# 5V_3V_LDO.net
KiCad netlist of a schematic drawn in Altium Designer
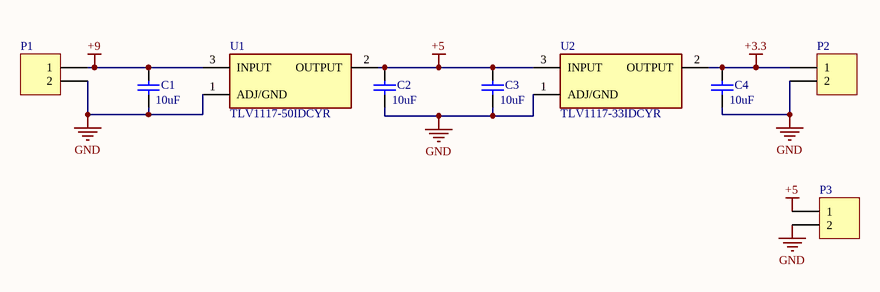
[diagram p0: 5V_3V_LDO.SchDoc]

(export (version "E")
  (design (tool "Eeschema 10.0.6"))
  (components
    (comp (ref "C1")
      (value "10uF")
      (footprint "0805 - Capacitor")
      (description "Nonpolarized Capacitor")
      (fields
        (field (name "MANUFACTURER") "Yageo")
        (field (name "MANUFACTURER PART NUMBER") "CC0805KKX5R8BB106")
      )
      (libsource (lib "General") (part "Capacitor - Nonpolarized"))
    )
    (comp (ref "C2")
      (value "10uF")
      (footprint "0805 - Capacitor")
      (description "Nonpolarized Capacitor")
      (fields
        (field (name "MANUFACTURER") "Yageo")
        (field (name "MANUFACTURER PART NUMBER") "CC0805KKX5R8BB106")
      )
      (libsource (lib "General") (part "Capacitor - Nonpolarized"))
    )
    (comp (ref "C3")
      (value "10uF")
      (footprint "0805 - Capacitor")
      (description "Nonpolarized Capacitor")
      (fields
        (field (name "MANUFACTURER") "Yageo")
        (field (name "MANUFACTURER PART NUMBER") "CC0805KKX5R8BB106")
      )
      (libsource (lib "General") (part "Capacitor - Nonpolarized"))
    )
    (comp (ref "C4")
      (value "10uF")
      (footprint "0805 - Capacitor")
      (description "Nonpolarized Capacitor")
      (fields
        (field (name "MANUFACTURER") "Yageo")
        (field (name "MANUFACTURER PART NUMBER") "CC0805KKX5R8BB106")
      )
      (libsource (lib "General") (part "Capacitor - Nonpolarized"))
    )
    (comp (ref "P1")
      (value "1x2 Header")
      (footprint "HDR1X2")
      (description "1x2 Pin Header")
      (libsource (lib "") (part "1x2 Header_1"))
    )
    (comp (ref "P2")
      (value "1x2 Header")
      (footprint "HDR1X2")
      (description "1x2 Pin Header")
      (libsource (lib "GeneralConnectors") (part "1x2 Header"))
    )
    (comp (ref "P3")
      (value "1x2 Header")
      (footprint "HDR1X2")
      (description "1x2 Pin Header")
      (libsource (lib "GeneralConnectors") (part "1x2 Header"))
    )
    (comp (ref "U1")
      (value "TLV1117-50IDCYR")
      (footprint "TLV1117")
      (description "Linear Voltage Regulator IC 5V 800MA SOT223-4")
      (fields
        (field (name "MANUFACTURER") "Texas Instruments")
        (field (name "DIGIKEY PART NUMBER") "296-21115-1-ND")
      )
      (libsource (lib "GeneralComponents") (part "TLV1117-50IDCYR"))
    )
    (comp (ref "U2")
      (value "TLV1117-33IDCYR")
      (footprint "TLV1117")
      (description "Linear Voltage Regulator IC 3.3V 800MA SOT223-4")
      (fields
        (field (name "MANUFACTURER") "Texas Instruments")
        (field (name "DIGIKEY PART NUMBER") "296-21112-1-ND")
      )
      (libsource (lib "GeneralComponents") (part "TLV1117-33IDCYR"))
    )
  )
  (nets
    (net (code "1") (name "+3.3") (class "Default")
      (node (ref "C4") (pin "2") (pinfunction "2_2") (pintype "passive"))
      (node (ref "P2") (pin "1") (pinfunction "1_1") (pintype "passive"))
      (node (ref "U2") (pin "2") (pinfunction "OUTPUT_2") (pintype "passive"))
    )
    (net (code "2") (name "+5") (class "Default")
      (node (ref "C2") (pin "2") (pinfunction "2_2") (pintype "passive"))
      (node (ref "C3") (pin "2") (pinfunction "2_2") (pintype "passive"))
      (node (ref "P3") (pin "1") (pinfunction "1_1") (pintype "passive"))
      (node (ref "U1") (pin "2") (pinfunction "OUTPUT_2") (pintype "passive"))
      (node (ref "U2") (pin "3") (pinfunction "INPUT_3") (pintype "passive"))
    )
    (net (code "3") (name "+9") (class "Default")
      (node (ref "C1") (pin "2") (pinfunction "2_2") (pintype "passive"))
      (node (ref "P1") (pin "1") (pinfunction "1_1") (pintype "passive"))
      (node (ref "U1") (pin "3") (pinfunction "INPUT_3") (pintype "passive"))
    )
    (net (code "4") (name "GND") (class "Default")
      (node (ref "C1") (pin "1") (pinfunction "1_1") (pintype "passive"))
      (node (ref "C2") (pin "1") (pinfunction "1_1") (pintype "passive"))
      (node (ref "C3") (pin "1") (pinfunction "1_1") (pintype "passive"))
      (node (ref "C4") (pin "1") (pinfunction "1_1") (pintype "passive"))
      (node (ref "P1") (pin "2") (pinfunction "2_2") (pintype "passive"))
      (node (ref "P2") (pin "2") (pinfunction "2_2") (pintype "passive"))
      (node (ref "P3") (pin "2") (pinfunction "2_2") (pintype "passive"))
      (node (ref "U1") (pin "1") (pinfunction "ADJ/GND_1") (pintype "passive"))
      (node (ref "U2") (pin "1") (pinfunction "ADJ/GND_1") (pintype "passive"))
    )
  )
)
